# connectors.net
KiCad netlist of a schematic drawn in Altium Designer
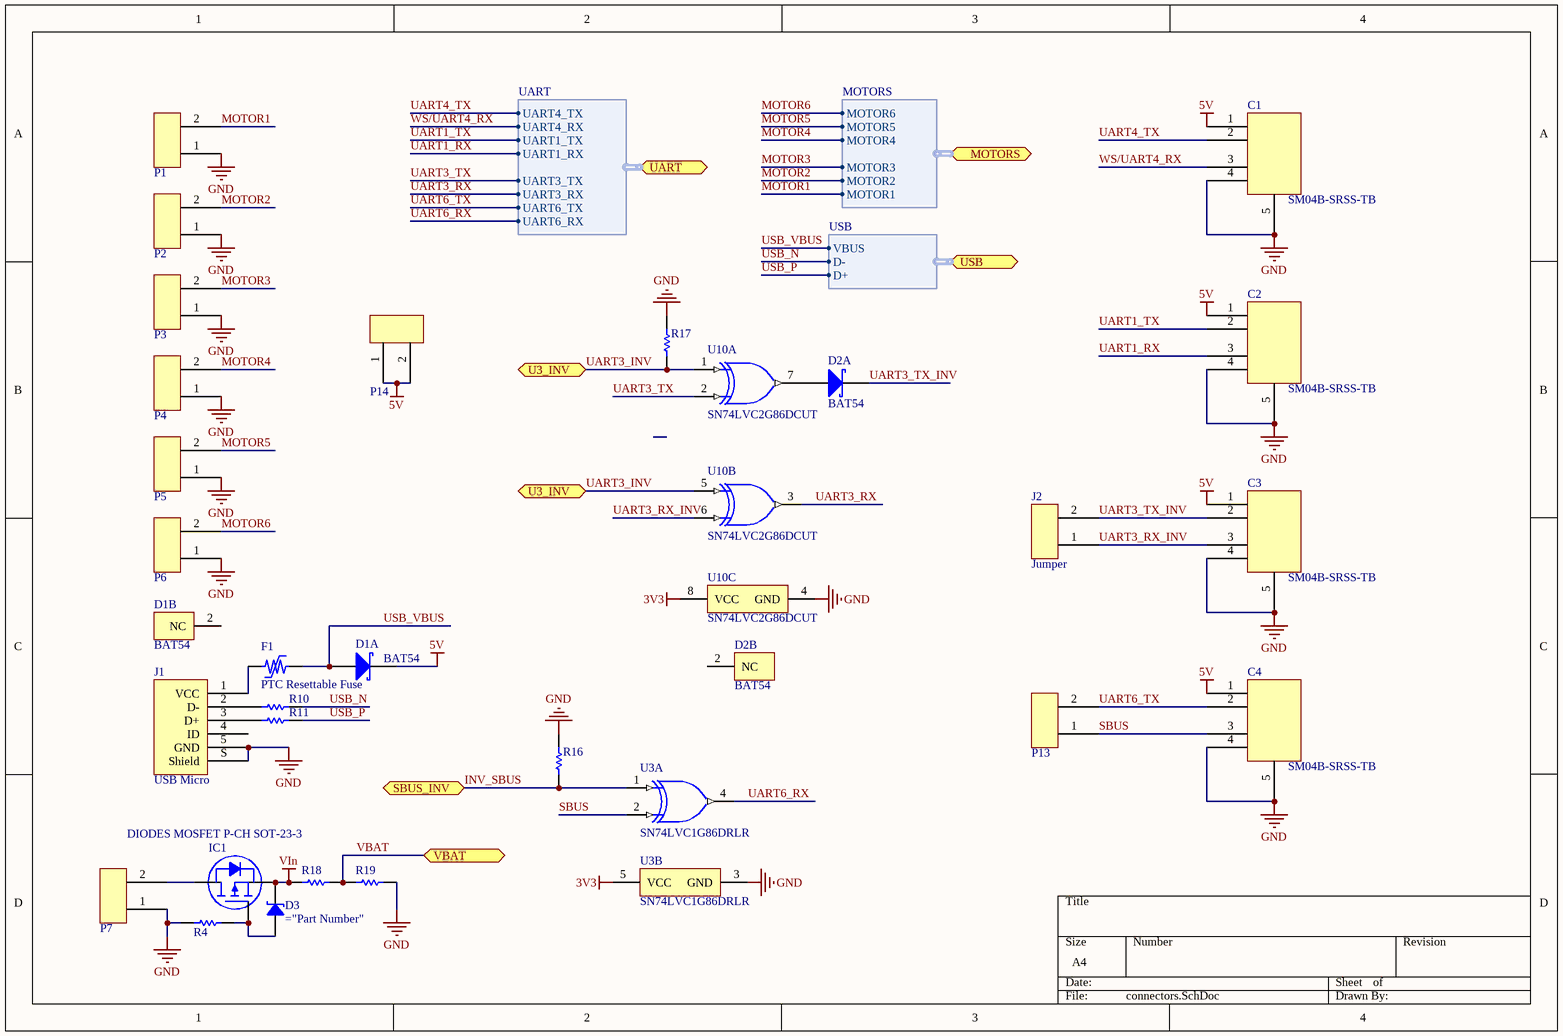
[diagram p0: connectors.SchDoc]

(export (version "E")
  (design (tool "Eeschema 10.0.6"))
  (components
    (comp (ref "C1")
      (value "SM04B-SRSS-TB")
      (footprint "SM04B-SRSS-TB")
      (description "JST SH 4-Pin Side Entry Housing")
      (libsource (lib "MyLib") (part "SM04B-SRSS-TB"))
    )
    (comp (ref "C2")
      (value "SM04B-SRSS-TB")
      (footprint "SM04B-SRSS-TB")
      (description "JST SH 4-Pin Side Entry Housing")
      (libsource (lib "MyLib") (part "SM04B-SRSS-TB"))
    )
    (comp (ref "C3")
      (value "SM04B-SRSS-TB")
      (footprint "SM04B-SRSS-TB")
      (description "JST SH 4-Pin Side Entry Housing")
      (libsource (lib "MyLib") (part "SM04B-SRSS-TB"))
    )
    (comp (ref "C4")
      (value "SM04B-SRSS-TB")
      (footprint "SM04B-SRSS-TB")
      (description "JST SH 4-Pin Side Entry Housing")
      (libsource (lib "MyLib") (part "SM04B-SRSS-TB"))
    )
    (comp (ref "D1")
      (value "BAT54")
      (footprint "NXP-SOT23-3_V")
      (description "Schottky Barrier Diode, 30 V, 2 uA, -55 to 150 degC, 3-Pin SOT23, RoHS, Tape and Reel")
      (fields (field (name "MANUFACTURER") "NXP Semiconductors"))
      (libsource (lib "") (part "NXP-DSKY_A1K3-3_1"))
    )
    (comp (ref "D2")
      (value "BAT54")
      (footprint "NXP-SOT23-3_V")
      (description "Schottky Barrier Diode, 30 V, 2 uA, -55 to 150 degC, 3-Pin SOT23, RoHS, Tape and Reel")
      (fields (field (name "MANUFACTURER") "NXP Semiconductors"))
      (libsource (lib "") (part "NXP-DSKY_A1K3-3_1"))
    )
    (comp (ref "D3")
      (value "~")
      (footprint "SOD-123")
      (description "Zener Diode")
      (libsource (lib "Diodes") (part "Diode Zener"))
    )
    (comp (ref "F1")
      (value "PTC Resettable Fuse")
      (footprint "other:F0805")
      (description "MF-PSMF Series - PTC Resettable Fuses")
      (fields (field (name "MANUFACTURER") "Bourns"))
      (libsource (lib "other") (part "PPTC"))
    )
    (comp (ref "IC1")
      (value "DIODES MOSFET P-CH SOT-23-3")
      (footprint "DIODES SOT-23-3")
      (libsource (lib "Celestial Library") (part "DIODES MOSFET P-CH SOT-23-3"))
    )
    (comp (ref "J1")
      (value "USB Micro")
      (footprint "FCI USB 10118193-0001LF")
      (libsource (lib "MyLib") (part "USB 2.0 Type B Micro"))
    )
    (comp (ref "J2") (value "Jumper") (footprint "Jumper") (libsource (lib "MyLib") (part "PCB Jumper")))
    (comp (ref "P1") (value "2Pads") (footprint "2Pads") (libsource (lib "MyLib") (part "2Pads")))
    (comp (ref "P2") (value "2Pads") (footprint "2Pads") (libsource (lib "MyLib") (part "2Pads")))
    (comp (ref "P3") (value "2Pads") (footprint "2Pads") (libsource (lib "MyLib") (part "2Pads")))
    (comp (ref "P4") (value "2Pads") (footprint "2Pads") (libsource (lib "MyLib") (part "2Pads")))
    (comp (ref "P5") (value "2Pads") (footprint "2Pads") (libsource (lib "MyLib") (part "2Pads")))
    (comp (ref "P6") (value "2Pads") (footprint "2Pads") (libsource (lib "MyLib") (part "2Pads")))
    (comp (ref "P7") (value "2Pads") (footprint "2Pads") (libsource (lib "MyLib") (part "2Pads")))
    (comp (ref "P13") (value "2 Pads") (footprint "other:2Pads") (libsource (lib "other") (part "2 Pads")))
    (comp (ref "P14") (value "2 Pads") (footprint "other:2Pads") (libsource (lib "") (part "2 Pads_1")))
    (comp (ref "R4")
      (value "100K 5% 0402(1005)")
      (footprint "RESC0402(1005)_L")
      (description "100K 0.063W 5% 0402 (1005 Metric)  SMD")
      (fields (field (name "POWER") "0.063 W") (field (name "TOLERANCE") "5 %"))
      (libsource (lib "Altium Content Vault") (part "RES"))
    )
    (comp (ref "R10")
      (value "22R 5% 0402(1005)")
      (footprint "RESC0402(1005)_M")
      (description "22R 0.063W 5% 0402 (1005 Metric)  SMD")
      (fields (field (name "POWER") "0.063 W") (field (name "TOLERANCE") "5 %"))
      (libsource (lib "Altium Content Vault") (part "RES"))
    )
    (comp (ref "R11")
      (value "22R 5% 0402(1005)")
      (footprint "RESC0402(1005)_M")
      (description "22R 0.063W 5% 0402 (1005 Metric)  SMD")
      (fields (field (name "POWER") "0.063 W") (field (name "TOLERANCE") "5 %"))
      (libsource (lib "Altium Content Vault") (part "RES"))
    )
    (comp (ref "R16")
      (value "10K 5% 0402(1005)")
      (footprint "RESC0402(1005)_L")
      (description "10K 0.063W 5% 0402 (1005 Metric)  SMD")
      (fields (field (name "TOLERANCE") "5 %") (field (name "POWER") "0.063 W"))
      (libsource (lib "Altium Content Vault") (part "CMP-1011-00098-1"))
    )
    (comp (ref "R17")
      (value "10K 5% 0402(1005)")
      (footprint "RESC0402(1005)_L")
      (description "10K 0.063W 5% 0402 (1005 Metric)  SMD")
      (fields (field (name "TOLERANCE") "5 %") (field (name "POWER") "0.063 W"))
      (libsource (lib "Altium Content Vault") (part "CMP-1011-00098-1"))
    )
    (comp (ref "R18")
      (value "10K 5% 0402(1005)")
      (footprint "RESC0402(1005)_L")
      (description "10K 0.063W 5% 0402 (1005 Metric)  SMD")
      (fields (field (name "TOLERANCE") "5 %") (field (name "POWER") "0.063 W"))
      (libsource (lib "Altium Content Vault") (part "RES"))
    )
    (comp (ref "R19")
      (value "1K 5% 0402(1005)")
      (footprint "RESC0402(1005)_L")
      (description "1K 0.063W 5% 0402 (1005 Metric)  SMD")
      (fields (field (name "TOLERANCE") "5 %") (field (name "POWER") "0.063 W"))
      (libsource (lib "Altium Content Vault") (part "RES"))
    )
    (comp (ref "U3")
      (value "SN74LVC1G86DRLR")
      (footprint "DRL0005A_M")
      (description "Single 2-Input Exclusive-OR Gate, DRL0005A, LARGE T&R")
      (fields
        (field (name "GENERIC PART NUMBER") "SN74LVC1G86")
        (field (name "MANUFACTURER") "Texas Instruments")
      )
      (libsource (lib "Altium Content Vault") (part "TI-XOR-1-2IN-5"))
    )
    (comp (ref "U10")
      (value "SN74LVC2G86DCUT")
      (footprint "DCU0008A_M")
      (description "Dual 2-Input Exclusive-Or Gate, DCU0008A, SMALL T&R")
      (fields
        (field (name "GENERIC PART NUMBER") "SN74LVC2G86")
        (field (name "MANUFACTURER") "Texas Instruments")
      )
      (libsource (lib "Altium Content Vault") (part "TI-XOR-2-2IN"))
    )
  )
  (nets
    (net (code "4") (name "/INV_SBUS") (class "Default")
      (node (ref "R16") (pin "1") (pinfunction "1_1") (pintype "passive"))
      (node (ref "U3") (pin "1") (pinfunction "A_1") (pintype "input"))
    )
    (net (code "5") (name "/MOTOR1") (class "Default")
      (node (ref "P1") (pin "2") (pinfunction "2_2") (pintype "passive"))
    )
    (net (code "6") (name "/MOTOR2") (class "Default")
      (node (ref "P2") (pin "2") (pinfunction "2_2") (pintype "passive"))
    )
    (net (code "7") (name "/MOTOR3") (class "Default")
      (node (ref "P3") (pin "2") (pinfunction "2_2") (pintype "passive"))
    )
    (net (code "8") (name "/MOTOR4") (class "Default")
      (node (ref "P4") (pin "2") (pinfunction "2_2") (pintype "passive"))
    )
    (net (code "9") (name "/MOTOR5") (class "Default")
      (node (ref "P5") (pin "2") (pinfunction "2_2") (pintype "passive"))
    )
    (net (code "10") (name "/MOTOR6") (class "Default")
      (node (ref "P6") (pin "2") (pinfunction "2_2") (pintype "passive"))
    )
    (net (code "11") (name "/SBUS") (class "Default")
      (node (ref "C4") (pin "3") (pinfunction "3_3") (pintype "passive"))
      (node (ref "P13") (pin "1") (pinfunction "1_1") (pintype "passive"))
      (node (ref "U3") (pin "2") (pinfunction "B_2") (pintype "input"))
    )
    (net (code "12") (name "/UART1_RX") (class "Default")
      (node (ref "C2") (pin "3") (pinfunction "3_3") (pintype "passive"))
    )
    (net (code "13") (name "/UART1_TX") (class "Default")
      (node (ref "C2") (pin "2") (pinfunction "2_2") (pintype "passive"))
    )
    (net (code "14") (name "/UART3_INV") (class "Default")
      (node (ref "R17") (pin "1") (pinfunction "1_1") (pintype "passive"))
      (node (ref "U10") (pin "1") (pinfunction "1A_1") (pintype "input"))
      (node (ref "U10") (pin "5") (pinfunction "2A_5") (pintype "input"))
    )
    (net (code "15") (name "/UART3_RX") (class "Default")
      (node (ref "U10") (pin "3") (pinfunction "2Y_3") (pintype "output"))
    )
    (net (code "16") (name "/UART3_RX_INV") (class "Default")
      (node (ref "C3") (pin "3") (pinfunction "3_3") (pintype "passive"))
      (node (ref "J2") (pin "1") (pinfunction "1_1") (pintype "passive"))
      (node (ref "U10") (pin "6") (pinfunction "2B_6") (pintype "input"))
    )
    (net (code "17") (name "/UART3_TX") (class "Default")
      (node (ref "U10") (pin "2") (pinfunction "1B_2") (pintype "input"))
    )
    (net (code "18") (name "/UART3_TX_INV") (class "Default")
      (node (ref "C3") (pin "2") (pinfunction "2_2") (pintype "passive"))
      (node (ref "D2") (pin "3") (pinfunction "K_3") (pintype "passive"))
      (node (ref "J2") (pin "2") (pinfunction "2_2") (pintype "passive"))
    )
    (net (code "19") (name "/UART4_TX") (class "Default")
      (node (ref "C1") (pin "2") (pinfunction "2_2") (pintype "passive"))
    )
    (net (code "20") (name "/UART6_RX") (class "Default")
      (node (ref "U3") (pin "4") (pinfunction "Y_4") (pintype "output"))
    )
    (net (code "21") (name "/UART6_TX") (class "Default")
      (node (ref "C4") (pin "2") (pinfunction "2_2") (pintype "passive"))
      (node (ref "P13") (pin "2") (pinfunction "2_2") (pintype "passive"))
    )
    (net (code "22") (name "/USB_N") (class "Default")
      (node (ref "R10") (pin "2") (pinfunction "2_2") (pintype "passive"))
    )
    (net (code "23") (name "/USB_P") (class "Default")
      (node (ref "R11") (pin "2") (pinfunction "2_2") (pintype "passive"))
    )
    (net (code "24") (name "/USB_VBUS") (class "Default")
      (node (ref "D1") (pin "1") (pinfunction "A_1") (pintype "passive"))
      (node (ref "F1") (pin "2") (pinfunction "2_2") (pintype "passive"))
    )
    (net (code "25") (name "/VBAT") (class "Default")
      (node (ref "R18") (pin "2") (pinfunction "2_2") (pintype "passive"))
      (node (ref "R19") (pin "1") (pinfunction "1_1") (pintype "passive"))
    )
    (net (code "26") (name "/WS{slash}UART4_RX") (class "Default")
      (node (ref "C1") (pin "3") (pinfunction "3_3") (pintype "passive"))
    )
    (net (code "30") (name "3V3") (class "Default")
      (node (ref "U10") (pin "8") (pinfunction "VCC_8") (pintype "power_in"))
      (node (ref "U3") (pin "5") (pinfunction "VCC_5") (pintype "power_in"))
    )
    (net (code "31") (name "5V") (class "Default")
      (node (ref "C1") (pin "1") (pinfunction "1_1") (pintype "passive"))
      (node (ref "C2") (pin "1") (pinfunction "1_1") (pintype "passive"))
      (node (ref "C3") (pin "1") (pinfunction "1_1") (pintype "passive"))
      (node (ref "C4") (pin "1") (pinfunction "1_1") (pintype "passive"))
      (node (ref "D1") (pin "3") (pinfunction "K_3") (pintype "passive"))
      (node (ref "P14") (pin "1") (pinfunction "1_1") (pintype "passive"))
      (node (ref "P14") (pin "2") (pinfunction "2_2") (pintype "passive"))
    )
    (net (code "32") (name "GND") (class "Default")
      (node (ref "C1") (pin "4") (pinfunction "4_4") (pintype "passive"))
      (node (ref "C1") (pin "5") (pinfunction "5_5") (pintype "passive"))
      (node (ref "C2") (pin "4") (pinfunction "4_4") (pintype "passive"))
      (node (ref "C2") (pin "5") (pinfunction "5_5") (pintype "passive"))
      (node (ref "C3") (pin "4") (pinfunction "4_4") (pintype "passive"))
      (node (ref "C3") (pin "5") (pinfunction "5_5") (pintype "passive"))
      (node (ref "C4") (pin "4") (pinfunction "4_4") (pintype "passive"))
      (node (ref "C4") (pin "5") (pinfunction "5_5") (pintype "passive"))
      (node (ref "J1") (pin "5") (pinfunction "GND_5") (pintype "passive"))
      (node (ref "J1") (pin "S") (pinfunction "Shield_S") (pintype "passive"))
      (node (ref "P1") (pin "1") (pinfunction "1_1") (pintype "passive"))
      (node (ref "P2") (pin "1") (pinfunction "1_1") (pintype "passive"))
      (node (ref "P3") (pin "1") (pinfunction "1_1") (pintype "passive"))
      (node (ref "P4") (pin "1") (pinfunction "1_1") (pintype "passive"))
      (node (ref "P5") (pin "1") (pinfunction "1_1") (pintype "passive"))
      (node (ref "P6") (pin "1") (pinfunction "1_1") (pintype "passive"))
      (node (ref "P7") (pin "1") (pinfunction "1_1") (pintype "passive"))
      (node (ref "R16") (pin "2") (pinfunction "2_2") (pintype "passive"))
      (node (ref "R17") (pin "2") (pinfunction "2_2") (pintype "passive"))
      (node (ref "R19") (pin "2") (pinfunction "2_2") (pintype "passive"))
      (node (ref "R4") (pin "1") (pinfunction "1_1") (pintype "passive"))
      (node (ref "U10") (pin "4") (pinfunction "GND_4") (pintype "power_in"))
      (node (ref "U3") (pin "3") (pinfunction "GND_3") (pintype "power_in"))
    )
    (net (code "33") (name "Net-(D2A-A)") (class "Default")
      (node (ref "D2") (pin "1") (pinfunction "A_1") (pintype "passive"))
      (node (ref "U10") (pin "7") (pinfunction "1Y_7") (pintype "output"))
    )
    (net (code "34") (name "Net-(IC1-D)") (class "Default")
      (node (ref "IC1") (pin "2") (pinfunction "D_2") (pintype "passive"))
      (node (ref "P7") (pin "2") (pinfunction "2_2") (pintype "passive"))
    )
    (net (code "35") (name "Net-(IC1-G)") (class "Default")
      (node (ref "D3") (pin "1") (pinfunction "1_1") (pintype "passive"))
      (node (ref "IC1") (pin "1") (pinfunction "G_1") (pintype "passive"))
      (node (ref "R4") (pin "2") (pinfunction "2_2") (pintype "passive"))
    )
    (net (code "36") (name "Net-(J1-D+)") (class "Default")
      (node (ref "J1") (pin "3") (pinfunction "D+_3") (pintype "passive"))
      (node (ref "R11") (pin "1") (pinfunction "1_1") (pintype "passive"))
    )
    (net (code "37") (name "Net-(J1-D-)") (class "Default")
      (node (ref "J1") (pin "2") (pinfunction "D-_2") (pintype "passive"))
      (node (ref "R10") (pin "1") (pinfunction "1_1") (pintype "passive"))
    )
    (net (code "38") (name "Net-(J1-VCC)") (class "Default")
      (node (ref "F1") (pin "1") (pinfunction "1_1") (pintype "passive"))
      (node (ref "J1") (pin "1") (pinfunction "VCC_1") (pintype "passive"))
    )
    (net (code "39") (name "VIn") (class "Default")
      (node (ref "D3") (pin "2") (pinfunction "2_2") (pintype "passive"))
      (node (ref "IC1") (pin "3") (pinfunction "S_3") (pintype "passive"))
      (node (ref "R18") (pin "1") (pinfunction "1_1") (pintype "passive"))
    )
    (net (code "40") (name "unconnected-(D1B-NC-Pad2)") (class "Default")
      (node (ref "D1") (pin "2") (pinfunction "NC_2") (pintype "passive"))
    )
    (net (code "41") (name "unconnected-(D2B-NC-Pad2)") (class "Default")
      (node (ref "D2") (pin "2") (pinfunction "NC_2") (pintype "passive"))
    )
    (net (code "42") (name "unconnected-(J1-ID-Pad4)") (class "Default")
      (node (ref "J1") (pin "4") (pinfunction "ID_4") (pintype "passive"))
    )
  )
)
